# Balancing.net
KiCad netlist of a schematic drawn in Altium Designer
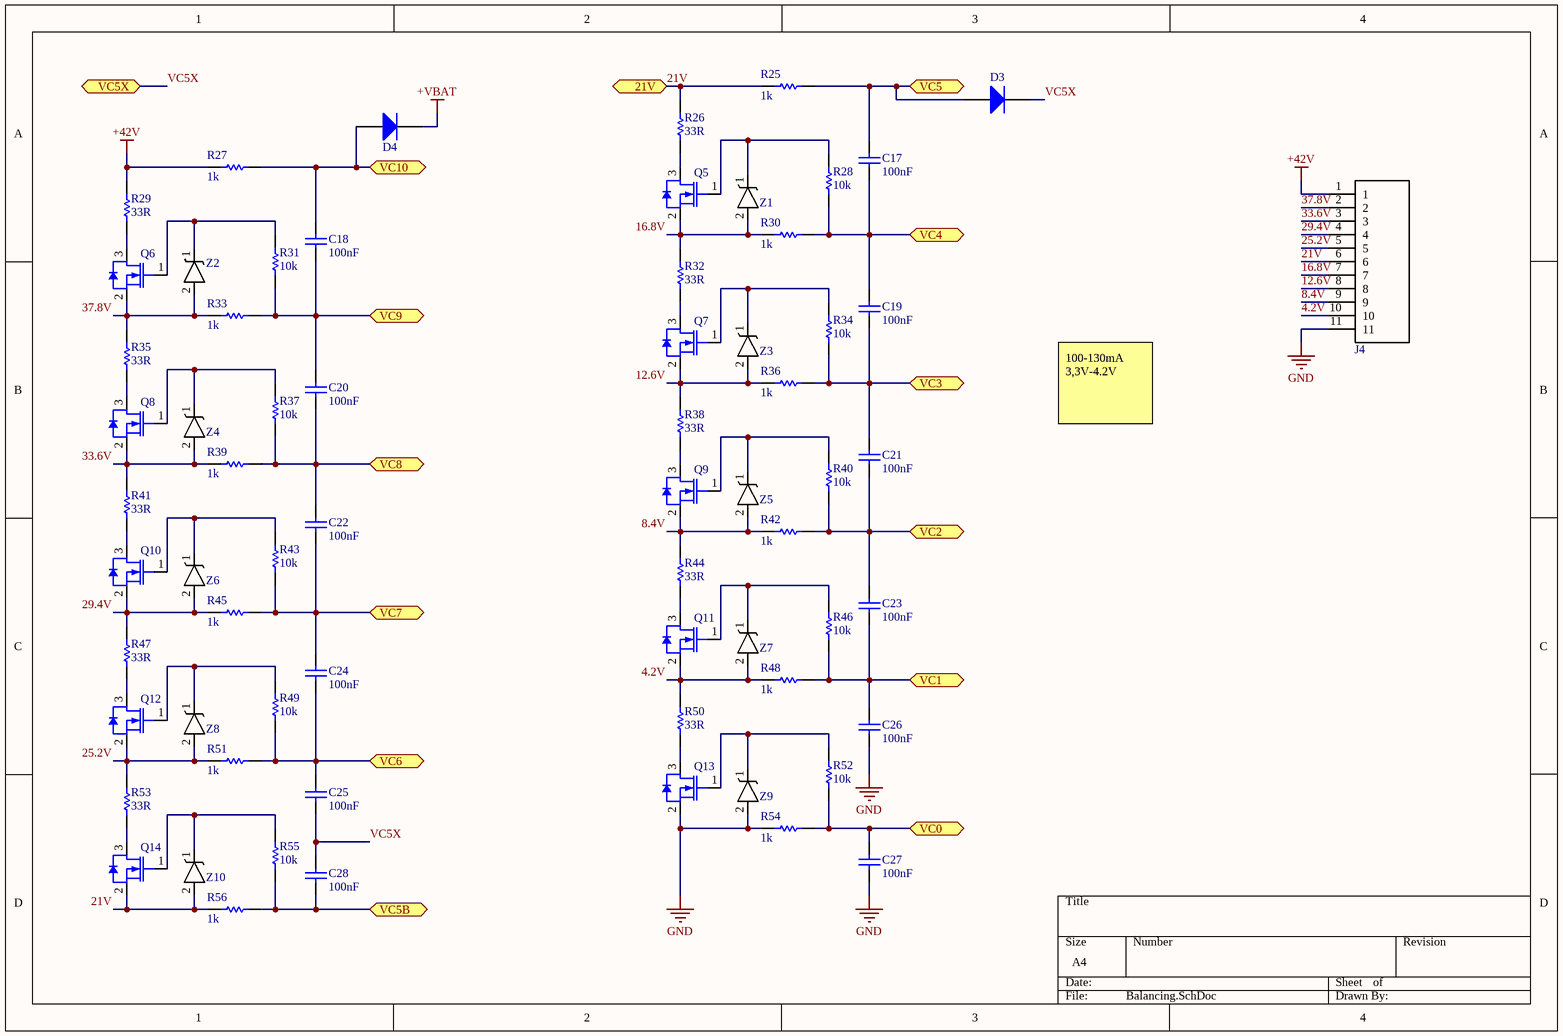
[diagram p0: Balancing.SchDoc]

(export (version "E")
  (design (tool "Eeschema 10.0.6"))
  (components
    (comp (ref "C17")
      (value "100nF")
      (footprint "Wurth 0603 capacitor")
      (fields (field (name "Comment") "Generic Capacitor 100nF 0603"))
      (libsource (lib "Passives") (part "Generic Capacitor 100nF 0603"))
    )
    (comp (ref "C18")
      (value "100nF")
      (footprint "Wurth 0603 capacitor")
      (fields (field (name "Comment") "Generic Capacitor 100nF 0603"))
      (libsource (lib "Passives") (part "Generic Capacitor 100nF 0603"))
    )
    (comp (ref "C19")
      (value "100nF")
      (footprint "Wurth 0603 capacitor")
      (fields (field (name "Comment") "Generic Capacitor 100nF 0603"))
      (libsource (lib "Passives") (part "Generic Capacitor 100nF 0603"))
    )
    (comp (ref "C20")
      (value "100nF")
      (footprint "Wurth 0603 capacitor")
      (fields (field (name "Comment") "Generic Capacitor 100nF 0603"))
      (libsource (lib "Passives") (part "Generic Capacitor 100nF 0603"))
    )
    (comp (ref "C21")
      (value "100nF")
      (footprint "Wurth 0603 capacitor")
      (fields (field (name "Comment") "Generic Capacitor 100nF 0603"))
      (libsource (lib "Passives") (part "Generic Capacitor 100nF 0603"))
    )
    (comp (ref "C22")
      (value "100nF")
      (footprint "Wurth 0603 capacitor")
      (fields (field (name "Comment") "Generic Capacitor 100nF 0603"))
      (libsource (lib "Passives") (part "Generic Capacitor 100nF 0603"))
    )
    (comp (ref "C23")
      (value "100nF")
      (footprint "Wurth 0603 capacitor")
      (fields (field (name "Comment") "Generic Capacitor 100nF 0603"))
      (libsource (lib "Passives") (part "Generic Capacitor 100nF 0603"))
    )
    (comp (ref "C24")
      (value "100nF")
      (footprint "Wurth 0603 capacitor")
      (fields (field (name "Comment") "Generic Capacitor 100nF 0603"))
      (libsource (lib "Passives") (part "Generic Capacitor 100nF 0603"))
    )
    (comp (ref "C25")
      (value "100nF")
      (footprint "Wurth 0603 capacitor")
      (fields (field (name "Comment") "Generic Capacitor 100nF 0603"))
      (libsource (lib "Passives") (part "Generic Capacitor 100nF 0603"))
    )
    (comp (ref "C26")
      (value "100nF")
      (footprint "Wurth 0603 capacitor")
      (fields (field (name "Comment") "Generic Capacitor 100nF 0603"))
      (libsource (lib "Passives") (part "Generic Capacitor 100nF 0603"))
    )
    (comp (ref "C27")
      (value "100nF")
      (footprint "Wurth 0603 capacitor")
      (fields (field (name "Comment") "Generic Capacitor 100nF 0603"))
      (libsource (lib "Passives") (part "Generic Capacitor 100nF 0603"))
    )
    (comp (ref "C28")
      (value "100nF")
      (footprint "Wurth 0603 capacitor")
      (fields (field (name "Comment") "Generic Capacitor 100nF 0603"))
      (libsource (lib "Passives") (part "Generic Capacitor 100nF 0603"))
    )
    (comp (ref "D3")
      (value "1N4148W-7-F")
      (footprint "DIOD-SOD123-2_V")
      (description "Fast Switching Diode, 100 V, 0.15 A, -65 to 150 degC, 2-Pin?SOD123, RoHS, Tape and Reel")
      (fields (field (name "MANUFACTURER") "DiodesIncorporated"))
      (libsource (lib "Altium Content Vault") (part "D-AK-2"))
    )
    (comp (ref "D4")
      (value "1N4148W-7-F")
      (footprint "DIOD-SOD123-2_V")
      (description "Fast Switching Diode, 100 V, 0.15 A, -65 to 150 degC, 2-Pin?SOD123, RoHS, Tape and Reel")
      (fields (field (name "MANUFACTURER") "DiodesIncorporated"))
      (libsource (lib "Altium Content Vault") (part "D-AK-2"))
    )
    (comp (ref "J4")
      (value "S11B-PH-K-S_LF__SN_")
      (footprint "SamacSys:S11BPHKSLFSN")
      (description "Connector")
      (fields (field (name "MANUFACTURER_PART_NUMBER") "S11B-PH-K-S(LF)(SN)"))
      (libsource (lib "*") (part "S11B-PH-K-S_LF__SN_"))
    )
    (comp (ref "Q5")
      (value "DMN2004K-7")
      (footprint "Leaded:Diodes SOT23-3")
      (description "MOSFET N-CH 20V 0.63A SOT23-3")
      (fields
        (field (name "OCTOPART") "https://octopart.com/dmn2004k-7-diodes+inc.-7127688")
        (field (name "MANUFACTURER") "Diodes Inc.")
      )
      (libsource (lib "N CHN FET") (part "Diodes DMN2004K-7"))
    )
    (comp (ref "Q6")
      (value "DMN2004K-7")
      (footprint "Leaded:Diodes SOT23-3")
      (description "MOSFET N-CH 20V 0.63A SOT23-3")
      (fields
        (field (name "OCTOPART") "https://octopart.com/dmn2004k-7-diodes+inc.-7127688")
        (field (name "MANUFACTURER") "Diodes Inc.")
      )
      (libsource (lib "N CHN FET") (part "Diodes DMN2004K-7"))
    )
    (comp (ref "Q7")
      (value "DMN2004K-7")
      (footprint "Leaded:Diodes SOT23-3")
      (description "MOSFET N-CH 20V 0.63A SOT23-3")
      (fields
        (field (name "OCTOPART") "https://octopart.com/dmn2004k-7-diodes+inc.-7127688")
        (field (name "MANUFACTURER") "Diodes Inc.")
      )
      (libsource (lib "N CHN FET") (part "Diodes DMN2004K-7"))
    )
    (comp (ref "Q8")
      (value "DMN2004K-7")
      (footprint "Leaded:Diodes SOT23-3")
      (description "MOSFET N-CH 20V 0.63A SOT23-3")
      (fields
        (field (name "OCTOPART") "https://octopart.com/dmn2004k-7-diodes+inc.-7127688")
        (field (name "MANUFACTURER") "Diodes Inc.")
      )
      (libsource (lib "N CHN FET") (part "Diodes DMN2004K-7"))
    )
    (comp (ref "Q9")
      (value "DMN2004K-7")
      (footprint "Leaded:Diodes SOT23-3")
      (description "MOSFET N-CH 20V 0.63A SOT23-3")
      (fields
        (field (name "OCTOPART") "https://octopart.com/dmn2004k-7-diodes+inc.-7127688")
        (field (name "MANUFACTURER") "Diodes Inc.")
      )
      (libsource (lib "N CHN FET") (part "Diodes DMN2004K-7"))
    )
    (comp (ref "Q10")
      (value "DMN2004K-7")
      (footprint "Leaded:Diodes SOT23-3")
      (description "MOSFET N-CH 20V 0.63A SOT23-3")
      (fields
        (field (name "OCTOPART") "https://octopart.com/dmn2004k-7-diodes+inc.-7127688")
        (field (name "MANUFACTURER") "Diodes Inc.")
      )
      (libsource (lib "N CHN FET") (part "Diodes DMN2004K-7"))
    )
    (comp (ref "Q11")
      (value "DMN2004K-7")
      (footprint "Leaded:Diodes SOT23-3")
      (description "MOSFET N-CH 20V 0.63A SOT23-3")
      (fields
        (field (name "OCTOPART") "https://octopart.com/dmn2004k-7-diodes+inc.-7127688")
        (field (name "MANUFACTURER") "Diodes Inc.")
      )
      (libsource (lib "N CHN FET") (part "Diodes DMN2004K-7"))
    )
    (comp (ref "Q12")
      (value "DMN2004K-7")
      (footprint "Leaded:Diodes SOT23-3")
      (description "MOSFET N-CH 20V 0.63A SOT23-3")
      (fields
        (field (name "OCTOPART") "https://octopart.com/dmn2004k-7-diodes+inc.-7127688")
        (field (name "MANUFACTURER") "Diodes Inc.")
      )
      (libsource (lib "N CHN FET") (part "Diodes DMN2004K-7"))
    )
    (comp (ref "Q13")
      (value "DMN2004K-7")
      (footprint "Leaded:Diodes SOT23-3")
      (description "MOSFET N-CH 20V 0.63A SOT23-3")
      (fields
        (field (name "OCTOPART") "https://octopart.com/dmn2004k-7-diodes+inc.-7127688")
        (field (name "MANUFACTURER") "Diodes Inc.")
      )
      (libsource (lib "N CHN FET") (part "Diodes DMN2004K-7"))
    )
    (comp (ref "Q14")
      (value "DMN2004K-7")
      (footprint "Leaded:Diodes SOT23-3")
      (description "MOSFET N-CH 20V 0.63A SOT23-3")
      (fields
        (field (name "OCTOPART") "https://octopart.com/dmn2004k-7-diodes+inc.-7127688")
        (field (name "MANUFACTURER") "Diodes Inc.")
      )
      (libsource (lib "N CHN FET") (part "Diodes DMN2004K-7"))
    )
    (comp (ref "R25")
      (value "1k")
      (footprint "Wurth 0603 Resistor")
      (fields (field (name "Comment") "CRCW060310K0FKEA"))
      (libsource (lib "Passives") (part "Generic Resistor 1k 0603"))
    )
    (comp (ref "R26")
      (value "33R")
      (footprint "Leadless:FOJAN 2010 Resistor")
      (description "33ohm ±1% 200V ±100ppm/℃ , 750mW, 1010")
      (fields (field (name "MANUFACTURER") "Fojan") (field (name "Comment") "FRC2010F33R0TS"))
      (libsource (lib "Passives") (part "FOJAN FRC2010F33R0TS"))
    )
    (comp (ref "R27")
      (value "1k")
      (footprint "Wurth 0603 Resistor")
      (fields (field (name "Comment") "CRCW060310K0FKEA"))
      (libsource (lib "Passives") (part "Generic Resistor 1k 0603"))
    )
    (comp (ref "R28")
      (value "10k")
      (footprint "Wurth 0603 Resistor")
      (fields (field (name "Comment") "Generic Resistor 10k 0603"))
      (libsource (lib "Passives") (part "Generic Resistor 10k 0603"))
    )
    (comp (ref "R29")
      (value "33R")
      (footprint "Leadless:FOJAN 2010 Resistor")
      (description "33ohm ±1% 200V ±100ppm/℃ , 750mW, 1010")
      (fields (field (name "MANUFACTURER") "Fojan") (field (name "Comment") "FRC2010F33R0TS"))
      (libsource (lib "Passives") (part "FOJAN FRC2010F33R0TS"))
    )
    (comp (ref "R30")
      (value "1k")
      (footprint "Wurth 0603 Resistor")
      (fields (field (name "Comment") "CRCW060310K0FKEA"))
      (libsource (lib "Passives") (part "Generic Resistor 1k 0603"))
    )
    (comp (ref "R31")
      (value "10k")
      (footprint "Wurth 0603 Resistor")
      (fields (field (name "Comment") "Generic Resistor 10k 0603"))
      (libsource (lib "Passives") (part "Generic Resistor 10k 0603"))
    )
    (comp (ref "R32")
      (value "33R")
      (footprint "Leadless:FOJAN 2010 Resistor")
      (description "33ohm ±1% 200V ±100ppm/℃ , 750mW, 1010")
      (fields (field (name "MANUFACTURER") "Fojan") (field (name "Comment") "FRC2010F33R0TS"))
      (libsource (lib "Passives") (part "FOJAN FRC2010F33R0TS"))
    )
    (comp (ref "R33")
      (value "1k")
      (footprint "Wurth 0603 Resistor")
      (fields (field (name "Comment") "CRCW060310K0FKEA"))
      (libsource (lib "Passives") (part "Generic Resistor 1k 0603"))
    )
    (comp (ref "R34")
      (value "10k")
      (footprint "Wurth 0603 Resistor")
      (fields (field (name "Comment") "Generic Resistor 10k 0603"))
      (libsource (lib "Passives") (part "Generic Resistor 10k 0603"))
    )
    (comp (ref "R35")
      (value "33R")
      (footprint "Leadless:FOJAN 2010 Resistor")
      (description "33ohm ±1% 200V ±100ppm/℃ , 750mW, 1010")
      (fields (field (name "MANUFACTURER") "Fojan") (field (name "Comment") "FRC2010F33R0TS"))
      (libsource (lib "Passives") (part "FOJAN FRC2010F33R0TS"))
    )
    (comp (ref "R36")
      (value "1k")
      (footprint "Wurth 0603 Resistor")
      (fields (field (name "Comment") "CRCW060310K0FKEA"))
      (libsource (lib "Passives") (part "Generic Resistor 1k 0603"))
    )
    (comp (ref "R37")
      (value "10k")
      (footprint "Wurth 0603 Resistor")
      (fields (field (name "Comment") "Generic Resistor 10k 0603"))
      (libsource (lib "Passives") (part "Generic Resistor 10k 0603"))
    )
    (comp (ref "R38")
      (value "33R")
      (footprint "Leadless:FOJAN 2010 Resistor")
      (description "33ohm ±1% 200V ±100ppm/℃ , 750mW, 1010")
      (fields (field (name "MANUFACTURER") "Fojan") (field (name "Comment") "FRC2010F33R0TS"))
      (libsource (lib "Passives") (part "FOJAN FRC2010F33R0TS"))
    )
    (comp (ref "R39")
      (value "1k")
      (footprint "Wurth 0603 Resistor")
      (fields (field (name "Comment") "CRCW060310K0FKEA"))
      (libsource (lib "Passives") (part "Generic Resistor 1k 0603"))
    )
    (comp (ref "R40")
      (value "10k")
      (footprint "Wurth 0603 Resistor")
      (fields (field (name "Comment") "Generic Resistor 10k 0603"))
      (libsource (lib "Passives") (part "Generic Resistor 10k 0603"))
    )
    (comp (ref "R41")
      (value "33R")
      (footprint "Leadless:FOJAN 2010 Resistor")
      (description "33ohm ±1% 200V ±100ppm/℃ , 750mW, 1010")
      (fields (field (name "MANUFACTURER") "Fojan") (field (name "Comment") "FRC2010F33R0TS"))
      (libsource (lib "Passives") (part "FOJAN FRC2010F33R0TS"))
    )
    (comp (ref "R42")
      (value "1k")
      (footprint "Wurth 0603 Resistor")
      (fields (field (name "Comment") "CRCW060310K0FKEA"))
      (libsource (lib "Passives") (part "Generic Resistor 1k 0603"))
    )
    (comp (ref "R43")
      (value "10k")
      (footprint "Wurth 0603 Resistor")
      (fields (field (name "Comment") "Generic Resistor 10k 0603"))
      (libsource (lib "Passives") (part "Generic Resistor 10k 0603"))
    )
    (comp (ref "R44")
      (value "33R")
      (footprint "Leadless:FOJAN 2010 Resistor")
      (description "33ohm ±1% 200V ±100ppm/℃ , 750mW, 1010")
      (fields (field (name "MANUFACTURER") "Fojan") (field (name "Comment") "FRC2010F33R0TS"))
      (libsource (lib "Passives") (part "FOJAN FRC2010F33R0TS"))
    )
    (comp (ref "R45")
      (value "1k")
      (footprint "Wurth 0603 Resistor")
      (fields (field (name "Comment") "CRCW060310K0FKEA"))
      (libsource (lib "Passives") (part "Generic Resistor 1k 0603"))
    )
    (comp (ref "R46")
      (value "10k")
      (footprint "Wurth 0603 Resistor")
      (fields (field (name "Comment") "Generic Resistor 10k 0603"))
      (libsource (lib "Passives") (part "Generic Resistor 10k 0603"))
    )
    (comp (ref "R47")
      (value "33R")
      (footprint "Leadless:FOJAN 2010 Resistor")
      (description "33ohm ±1% 200V ±100ppm/℃ , 750mW, 1010")
      (fields (field (name "MANUFACTURER") "Fojan") (field (name "Comment") "FRC2010F33R0TS"))
      (libsource (lib "Passives") (part "FOJAN FRC2010F33R0TS"))
    )
    (comp (ref "R48")
      (value "1k")
      (footprint "Wurth 0603 Resistor")
      (fields (field (name "Comment") "CRCW060310K0FKEA"))
      (libsource (lib "Passives") (part "Generic Resistor 1k 0603"))
    )
    (comp (ref "R49")
      (value "10k")
      (footprint "Wurth 0603 Resistor")
      (fields (field (name "Comment") "Generic Resistor 10k 0603"))
      (libsource (lib "Passives") (part "Generic Resistor 10k 0603"))
    )
    (comp (ref "R50")
      (value "33R")
      (footprint "Leadless:FOJAN 2010 Resistor")
      (description "33ohm ±1% 200V ±100ppm/℃ , 750mW, 1010")
      (fields (field (name "MANUFACTURER") "Fojan") (field (name "Comment") "FRC2010F33R0TS"))
      (libsource (lib "Passives") (part "FOJAN FRC2010F33R0TS"))
    )
    (comp (ref "R51")
      (value "1k")
      (footprint "Wurth 0603 Resistor")
      (fields (field (name "Comment") "CRCW060310K0FKEA"))
      (libsource (lib "Passives") (part "Generic Resistor 1k 0603"))
    )
    (comp (ref "R52")
      (value "10k")
      (footprint "Wurth 0603 Resistor")
      (fields (field (name "Comment") "Generic Resistor 10k 0603"))
      (libsource (lib "Passives") (part "Generic Resistor 10k 0603"))
    )
    (comp (ref "R53")
      (value "33R")
      (footprint "Leadless:FOJAN 2010 Resistor")
      (description "33ohm ±1% 200V ±100ppm/℃ , 750mW, 1010")
      (fields (field (name "MANUFACTURER") "Fojan") (field (name "Comment") "FRC2010F33R0TS"))
      (libsource (lib "Passives") (part "FOJAN FRC2010F33R0TS"))
    )
    (comp (ref "R54")
      (value "1k")
      (footprint "Wurth 0603 Resistor")
      (fields (field (name "Comment") "CRCW060310K0FKEA"))
      (libsource (lib "Passives") (part "Generic Resistor 1k 0603"))
    )
    (comp (ref "R55")
      (value "10k")
      (footprint "Wurth 0603 Resistor")
      (fields (field (name "Comment") "Generic Resistor 10k 0603"))
      (libsource (lib "Passives") (part "Generic Resistor 10k 0603"))
    )
    (comp (ref "R56")
      (value "1k")
      (footprint "Wurth 0603 Resistor")
      (fields (field (name "Comment") "CRCW060310K0FKEA"))
      (libsource (lib "Passives") (part "Generic Resistor 1k 0603"))
    )
    (comp (ref "Z1")
      (value "MMSZ5232BS-7-F")
      (footprint "Diodes SOD-323")
      (description "Zener Diode")
      (fields (field (name "MOUSER PART NUMBER") "621-MMSZ5232BS-F"))
      (libsource (lib "Diodes") (part "Diodes MMSZ5232BS-7-F"))
    )
    (comp (ref "Z2")
      (value "MMSZ5232BS-7-F")
      (footprint "Diodes SOD-323")
      (description "Zener Diode")
      (fields (field (name "MOUSER PART NUMBER") "621-MMSZ5232BS-F"))
      (libsource (lib "Diodes") (part "Diodes MMSZ5232BS-7-F"))
    )
    (comp (ref "Z3")
      (value "MMSZ5232BS-7-F")
      (footprint "Diodes SOD-323")
      (description "Zener Diode")
      (fields (field (name "MOUSER PART NUMBER") "621-MMSZ5232BS-F"))
      (libsource (lib "Diodes") (part "Diodes MMSZ5232BS-7-F"))
    )
    (comp (ref "Z4")
      (value "MMSZ5232BS-7-F")
      (footprint "Diodes SOD-323")
      (description "Zener Diode")
      (fields (field (name "MOUSER PART NUMBER") "621-MMSZ5232BS-F"))
      (libsource (lib "Diodes") (part "Diodes MMSZ5232BS-7-F"))
    )
    (comp (ref "Z5")
      (value "MMSZ5232BS-7-F")
      (footprint "Diodes SOD-323")
      (description "Zener Diode")
      (fields (field (name "MOUSER PART NUMBER") "621-MMSZ5232BS-F"))
      (libsource (lib "Diodes") (part "Diodes MMSZ5232BS-7-F"))
    )
    (comp (ref "Z6")
      (value "MMSZ5232BS-7-F")
      (footprint "Diodes SOD-323")
      (description "Zener Diode")
      (fields (field (name "MOUSER PART NUMBER") "621-MMSZ5232BS-F"))
      (libsource (lib "Diodes") (part "Diodes MMSZ5232BS-7-F"))
    )
    (comp (ref "Z7")
      (value "MMSZ5232BS-7-F")
      (footprint "Diodes SOD-323")
      (description "Zener Diode")
      (fields (field (name "MOUSER PART NUMBER") "621-MMSZ5232BS-F"))
      (libsource (lib "Diodes") (part "Diodes MMSZ5232BS-7-F"))
    )
    (comp (ref "Z8")
      (value "MMSZ5232BS-7-F")
      (footprint "Diodes SOD-323")
      (description "Zener Diode")
      (fields (field (name "MOUSER PART NUMBER") "621-MMSZ5232BS-F"))
      (libsource (lib "Diodes") (part "Diodes MMSZ5232BS-7-F"))
    )
    (comp (ref "Z9")
      (value "MMSZ5232BS-7-F")
      (footprint "Diodes SOD-323")
      (description "Zener Diode")
      (fields (field (name "MOUSER PART NUMBER") "621-MMSZ5232BS-F"))
      (libsource (lib "Diodes") (part "Diodes MMSZ5232BS-7-F"))
    )
    (comp (ref "Z10")
      (value "MMSZ5232BS-7-F")
      (footprint "Diodes SOD-323")
      (description "Zener Diode")
      (fields (field (name "MOUSER PART NUMBER") "621-MMSZ5232BS-F"))
      (libsource (lib "Diodes") (part "Diodes MMSZ5232BS-7-F"))
    )
  )
  (nets
    (net (code "1") (name "+42V") (class "Default")
      (node (ref "J4") (pin "1") (pinfunction "1_1") (pintype "passive"))
      (node (ref "R27") (pin "2") (pinfunction "2_2") (pintype "passive"))
      (node (ref "R29") (pin "2") (pinfunction "2_2") (pintype "passive"))
    )
    (net (code "2") (name "+VBAT") (class "Default")
      (node (ref "D4") (pin "2") (pinfunction "K_2") (pintype "passive"))
    )
    (net (code "3") (name "/4.2V") (class "Default")
      (node (ref "J4") (pin "10") (pinfunction "10_10") (pintype "passive"))
      (node (ref "Q11") (pin "2") (pinfunction "S_2") (pintype "passive"))
      (node (ref "R48") (pin "2") (pinfunction "2_2") (pintype "passive"))
      (node (ref "R50") (pin "2") (pinfunction "2_2") (pintype "passive"))
      (node (ref "Z7") (pin "2") (pinfunction "A_2") (pintype "passive"))
    )
    (net (code "4") (name "/8.4V") (class "Default")
      (node (ref "J4") (pin "9") (pinfunction "9_9") (pintype "passive"))
      (node (ref "Q9") (pin "2") (pinfunction "S_2") (pintype "passive"))
      (node (ref "R42") (pin "2") (pinfunction "2_2") (pintype "passive"))
      (node (ref "R44") (pin "2") (pinfunction "2_2") (pintype "passive"))
      (node (ref "Z5") (pin "2") (pinfunction "A_2") (pintype "passive"))
    )
    (net (code "5") (name "/12.6V") (class "Default")
      (node (ref "J4") (pin "8") (pinfunction "8_8") (pintype "passive"))
      (node (ref "Q7") (pin "2") (pinfunction "S_2") (pintype "passive"))
      (node (ref "R36") (pin "2") (pinfunction "2_2") (pintype "passive"))
      (node (ref "R38") (pin "2") (pinfunction "2_2") (pintype "passive"))
      (node (ref "Z3") (pin "2") (pinfunction "A_2") (pintype "passive"))
    )
    (net (code "6") (name "/16.8V") (class "Default")
      (node (ref "J4") (pin "7") (pinfunction "7_7") (pintype "passive"))
      (node (ref "Q5") (pin "2") (pinfunction "S_2") (pintype "passive"))
      (node (ref "R30") (pin "2") (pinfunction "2_2") (pintype "passive"))
      (node (ref "R32") (pin "2") (pinfunction "2_2") (pintype "passive"))
      (node (ref "Z1") (pin "2") (pinfunction "A_2") (pintype "passive"))
    )
    (net (code "7") (name "/21V") (class "Default")
      (node (ref "J4") (pin "6") (pinfunction "6_6") (pintype "passive"))
      (node (ref "Q14") (pin "2") (pinfunction "S_2") (pintype "passive"))
      (node (ref "R25") (pin "2") (pinfunction "2_2") (pintype "passive"))
      (node (ref "R26") (pin "2") (pinfunction "2_2") (pintype "passive"))
      (node (ref "R56") (pin "2") (pinfunction "2_2") (pintype "passive"))
      (node (ref "Z10") (pin "2") (pinfunction "A_2") (pintype "passive"))
    )
    (net (code "8") (name "/25.2V") (class "Default")
      (node (ref "J4") (pin "5") (pinfunction "5_5") (pintype "passive"))
      (node (ref "Q12") (pin "2") (pinfunction "S_2") (pintype "passive"))
      (node (ref "R51") (pin "2") (pinfunction "2_2") (pintype "passive"))
      (node (ref "R53") (pin "2") (pinfunction "2_2") (pintype "passive"))
      (node (ref "Z8") (pin "2") (pinfunction "A_2") (pintype "passive"))
    )
    (net (code "9") (name "/29.4V") (class "Default")
      (node (ref "J4") (pin "4") (pinfunction "4_4") (pintype "passive"))
      (node (ref "Q10") (pin "2") (pinfunction "S_2") (pintype "passive"))
      (node (ref "R45") (pin "2") (pinfunction "2_2") (pintype "passive"))
      (node (ref "R47") (pin "2") (pinfunction "2_2") (pintype "passive"))
      (node (ref "Z6") (pin "2") (pinfunction "A_2") (pintype "passive"))
    )
    (net (code "10") (name "/33.6V") (class "Default")
      (node (ref "J4") (pin "3") (pinfunction "3_3") (pintype "passive"))
      (node (ref "Q8") (pin "2") (pinfunction "S_2") (pintype "passive"))
      (node (ref "R39") (pin "2") (pinfunction "2_2") (pintype "passive"))
      (node (ref "R41") (pin "2") (pinfunction "2_2") (pintype "passive"))
      (node (ref "Z4") (pin "2") (pinfunction "A_2") (pintype "passive"))
    )
    (net (code "11") (name "/37.8V") (class "Default")
      (node (ref "J4") (pin "2") (pinfunction "2_2") (pintype "passive"))
      (node (ref "Q6") (pin "2") (pinfunction "S_2") (pintype "passive"))
      (node (ref "R33") (pin "2") (pinfunction "2_2") (pintype "passive"))
      (node (ref "R35") (pin "2") (pinfunction "2_2") (pintype "passive"))
      (node (ref "Z2") (pin "2") (pinfunction "A_2") (pintype "passive"))
    )
    (net (code "12") (name "/VC0") (class "Default")
      (node (ref "C27") (pin "2") (pinfunction "2_2") (pintype "passive"))
      (node (ref "R52") (pin "1") (pinfunction "1_1") (pintype "passive"))
      (node (ref "R54") (pin "1") (pinfunction "1_1") (pintype "passive"))
    )
    (net (code "13") (name "/VC1") (class "Default")
      (node (ref "C23") (pin "1") (pinfunction "1_1") (pintype "passive"))
      (node (ref "C26") (pin "2") (pinfunction "2_2") (pintype "passive"))
      (node (ref "R46") (pin "1") (pinfunction "1_1") (pintype "passive"))
      (node (ref "R48") (pin "1") (pinfunction "1_1") (pintype "passive"))
    )
    (net (code "14") (name "/VC2") (class "Default")
      (node (ref "C21") (pin "1") (pinfunction "1_1") (pintype "passive"))
      (node (ref "C23") (pin "2") (pinfunction "2_2") (pintype "passive"))
      (node (ref "R40") (pin "1") (pinfunction "1_1") (pintype "passive"))
      (node (ref "R42") (pin "1") (pinfunction "1_1") (pintype "passive"))
    )
    (net (code "15") (name "/VC3") (class "Default")
      (node (ref "C19") (pin "1") (pinfunction "1_1") (pintype "passive"))
      (node (ref "C21") (pin "2") (pinfunction "2_2") (pintype "passive"))
      (node (ref "R34") (pin "1") (pinfunction "1_1") (pintype "passive"))
      (node (ref "R36") (pin "1") (pinfunction "1_1") (pintype "passive"))
    )
    (net (code "16") (name "/VC4") (class "Default")
      (node (ref "C17") (pin "1") (pinfunction "1_1") (pintype "passive"))
      (node (ref "C19") (pin "2") (pinfunction "2_2") (pintype "passive"))
      (node (ref "R28") (pin "1") (pinfunction "1_1") (pintype "passive"))
      (node (ref "R30") (pin "1") (pinfunction "1_1") (pintype "passive"))
    )
    (net (code "17") (name "/VC5") (class "Default")
      (node (ref "C17") (pin "2") (pinfunction "2_2") (pintype "passive"))
      (node (ref "D3") (pin "1") (pinfunction "A_1") (pintype "passive"))
      (node (ref "R25") (pin "1") (pinfunction "1_1") (pintype "passive"))
    )
    (net (code "18") (name "/VC5B") (class "Default")
      (node (ref "C28") (pin "1") (pinfunction "1_1") (pintype "passive"))
      (node (ref "R55") (pin "1") (pinfunction "1_1") (pintype "passive"))
      (node (ref "R56") (pin "1") (pinfunction "1_1") (pintype "passive"))
    )
    (net (code "19") (name "/VC5X") (class "Default")
      (node (ref "C25") (pin "1") (pinfunction "1_1") (pintype "passive"))
      (node (ref "C28") (pin "2") (pinfunction "2_2") (pintype "passive"))
      (node (ref "D3") (pin "2") (pinfunction "K_2") (pintype "passive"))
    )
    (net (code "20") (name "/VC6") (class "Default")
      (node (ref "C24") (pin "1") (pinfunction "1_1") (pintype "passive"))
      (node (ref "C25") (pin "2") (pinfunction "2_2") (pintype "passive"))
      (node (ref "R49") (pin "1") (pinfunction "1_1") (pintype "passive"))
      (node (ref "R51") (pin "1") (pinfunction "1_1") (pintype "passive"))
    )
    (net (code "21") (name "/VC7") (class "Default")
      (node (ref "C22") (pin "1") (pinfunction "1_1") (pintype "passive"))
      (node (ref "C24") (pin "2") (pinfunction "2_2") (pintype "passive"))
      (node (ref "R43") (pin "1") (pinfunction "1_1") (pintype "passive"))
      (node (ref "R45") (pin "1") (pinfunction "1_1") (pintype "passive"))
    )
    (net (code "22") (name "/VC8") (class "Default")
      (node (ref "C20") (pin "1") (pinfunction "1_1") (pintype "passive"))
      (node (ref "C22") (pin "2") (pinfunction "2_2") (pintype "passive"))
      (node (ref "R37") (pin "1") (pinfunction "1_1") (pintype "passive"))
      (node (ref "R39") (pin "1") (pinfunction "1_1") (pintype "passive"))
    )
    (net (code "23") (name "/VC9") (class "Default")
      (node (ref "C18") (pin "1") (pinfunction "1_1") (pintype "passive"))
      (node (ref "C20") (pin "2") (pinfunction "2_2") (pintype "passive"))
      (node (ref "R31") (pin "1") (pinfunction "1_1") (pintype "passive"))
      (node (ref "R33") (pin "1") (pinfunction "1_1") (pintype "passive"))
    )
    (net (code "24") (name "/VC10") (class "Default")
      (node (ref "C18") (pin "2") (pinfunction "2_2") (pintype "passive"))
      (node (ref "D4") (pin "1") (pinfunction "A_1") (pintype "passive"))
      (node (ref "R27") (pin "1") (pinfunction "1_1") (pintype "passive"))
    )
    (net (code "25") (name "GND") (class "Default")
      (node (ref "C26") (pin "1") (pinfunction "1_1") (pintype "passive"))
      (node (ref "C27") (pin "1") (pinfunction "1_1") (pintype "passive"))
      (node (ref "J4") (pin "11") (pinfunction "11_11") (pintype "passive"))
      (node (ref "Q13") (pin "2") (pinfunction "S_2") (pintype "passive"))
      (node (ref "R54") (pin "2") (pinfunction "2_2") (pintype "passive"))
      (node (ref "Z9") (pin "2") (pinfunction "A_2") (pintype "passive"))
    )
    (net (code "26") (name "Net-(Q5-D)") (class "Default")
      (node (ref "Q5") (pin "3") (pinfunction "D_3") (pintype "passive"))
      (node (ref "R26") (pin "1") (pinfunction "1_1") (pintype "passive"))
    )
    (net (code "27") (name "Net-(Q5-G)") (class "Default")
      (node (ref "Q5") (pin "1") (pinfunction "G_1") (pintype "passive"))
      (node (ref "R28") (pin "2") (pinfunction "2_2") (pintype "passive"))
      (node (ref "Z1") (pin "1") (pinfunction "K_1") (pintype "passive"))
    )
    (net (code "28") (name "Net-(Q6-D)") (class "Default")
      (node (ref "Q6") (pin "3") (pinfunction "D_3") (pintype "passive"))
      (node (ref "R29") (pin "1") (pinfunction "1_1") (pintype "passive"))
    )
    (net (code "29") (name "Net-(Q6-G)") (class "Default")
      (node (ref "Q6") (pin "1") (pinfunction "G_1") (pintype "passive"))
      (node (ref "R31") (pin "2") (pinfunction "2_2") (pintype "passive"))
      (node (ref "Z2") (pin "1") (pinfunction "K_1") (pintype "passive"))
    )
    (net (code "30") (name "Net-(Q7-D)") (class "Default")
      (node (ref "Q7") (pin "3") (pinfunction "D_3") (pintype "passive"))
      (node (ref "R32") (pin "1") (pinfunction "1_1") (pintype "passive"))
    )
    (net (code "31") (name "Net-(Q7-G)") (class "Default")
      (node (ref "Q7") (pin "1") (pinfunction "G_1") (pintype "passive"))
      (node (ref "R34") (pin "2") (pinfunction "2_2") (pintype "passive"))
      (node (ref "Z3") (pin "1") (pinfunction "K_1") (pintype "passive"))
    )
    (net (code "32") (name "Net-(Q8-D)") (class "Default")
      (node (ref "Q8") (pin "3") (pinfunction "D_3") (pintype "passive"))
      (node (ref "R35") (pin "1") (pinfunction "1_1") (pintype "passive"))
    )
    (net (code "33") (name "Net-(Q8-G)") (class "Default")
      (node (ref "Q8") (pin "1") (pinfunction "G_1") (pintype "passive"))
      (node (ref "R37") (pin "2") (pinfunction "2_2") (pintype "passive"))
      (node (ref "Z4") (pin "1") (pinfunction "K_1") (pintype "passive"))
    )
    (net (code "34") (name "Net-(Q9-D)") (class "Default")
      (node (ref "Q9") (pin "3") (pinfunction "D_3") (pintype "passive"))
      (node (ref "R38") (pin "1") (pinfunction "1_1") (pintype "passive"))
    )
    (net (code "35") (name "Net-(Q9-G)") (class "Default")
      (node (ref "Q9") (pin "1") (pinfunction "G_1") (pintype "passive"))
      (node (ref "R40") (pin "2") (pinfunction "2_2") (pintype "passive"))
      (node (ref "Z5") (pin "1") (pinfunction "K_1") (pintype "passive"))
    )
    (net (code "36") (name "Net-(Q10-D)") (class "Default")
      (node (ref "Q10") (pin "3") (pinfunction "D_3") (pintype "passive"))
      (node (ref "R41") (pin "1") (pinfunction "1_1") (pintype "passive"))
    )
    (net (code "37") (name "Net-(Q10-G)") (class "Default")
      (node (ref "Q10") (pin "1") (pinfunction "G_1") (pintype "passive"))
      (node (ref "R43") (pin "2") (pinfunction "2_2") (pintype "passive"))
      (node (ref "Z6") (pin "1") (pinfunction "K_1") (pintype "passive"))
    )
    (net (code "38") (name "Net-(Q11-D)") (class "Default")
      (node (ref "Q11") (pin "3") (pinfunction "D_3") (pintype "passive"))
      (node (ref "R44") (pin "1") (pinfunction "1_1") (pintype "passive"))
    )
    (net (code "39") (name "Net-(Q11-G)") (class "Default")
      (node (ref "Q11") (pin "1") (pinfunction "G_1") (pintype "passive"))
      (node (ref "R46") (pin "2") (pinfunction "2_2") (pintype "passive"))
      (node (ref "Z7") (pin "1") (pinfunction "K_1") (pintype "passive"))
    )
    (net (code "40") (name "Net-(Q12-D)") (class "Default")
      (node (ref "Q12") (pin "3") (pinfunction "D_3") (pintype "passive"))
      (node (ref "R47") (pin "1") (pinfunction "1_1") (pintype "passive"))
    )
    (net (code "41") (name "Net-(Q12-G)") (class "Default")
      (node (ref "Q12") (pin "1") (pinfunction "G_1") (pintype "passive"))
      (node (ref "R49") (pin "2") (pinfunction "2_2") (pintype "passive"))
      (node (ref "Z8") (pin "1") (pinfunction "K_1") (pintype "passive"))
    )
    (net (code "42") (name "Net-(Q13-D)") (class "Default")
      (node (ref "Q13") (pin "3") (pinfunction "D_3") (pintype "passive"))
      (node (ref "R50") (pin "1") (pinfunction "1_1") (pintype "passive"))
    )
    (net (code "43") (name "Net-(Q13-G)") (class "Default")
      (node (ref "Q13") (pin "1") (pinfunction "G_1") (pintype "passive"))
      (node (ref "R52") (pin "2") (pinfunction "2_2") (pintype "passive"))
      (node (ref "Z9") (pin "1") (pinfunction "K_1") (pintype "passive"))
    )
    (net (code "44") (name "Net-(Q14-D)") (class "Default")
      (node (ref "Q14") (pin "3") (pinfunction "D_3") (pintype "passive"))
      (node (ref "R53") (pin "1") (pinfunction "1_1") (pintype "passive"))
    )
    (net (code "45") (name "Net-(Q14-G)") (class "Default")
      (node (ref "Q14") (pin "1") (pinfunction "G_1") (pintype "passive"))
      (node (ref "R55") (pin "2") (pinfunction "2_2") (pintype "passive"))
      (node (ref "Z10") (pin "1") (pinfunction "K_1") (pintype "passive"))
    )
  )
)
